# HL1102.net
KiCad netlist of a schematic drawn in Altium Designer
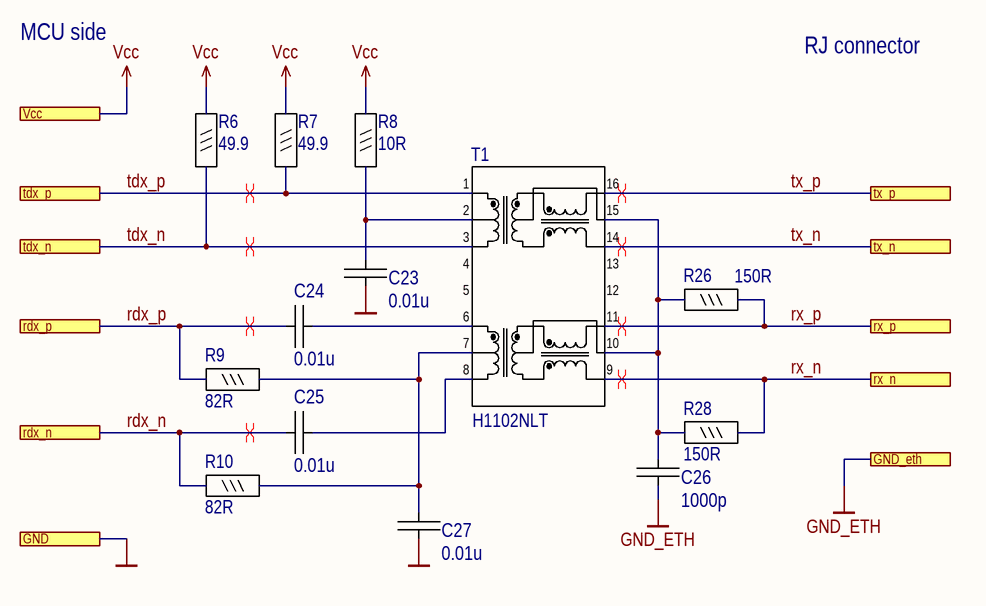
[diagram p0: HL1102.SchDoc]

(export (version "E")
  (design (tool "Eeschema 10.0.6"))
  (components
    (comp (ref "C23")
      (value "0.01u")
      (footprint "C0603_IPC")
      (description "0.01uF ±10% 50V Ceramic Capacitor X7R 0603 (1608 Metric)")
      (fields (field (name "PARTNUMBER") "0.01u 50V") (field (name "MPN") "CC0603KRX7R9BB103"))
      (libsource (lib "DB_res_cap_ind") (part "C0603_GOST"))
    )
    (comp (ref "C24")
      (value "0.01u")
      (footprint "C0603_IPC")
      (description "0.01uF ±10% 50V Ceramic Capacitor X7R 0603 (1608 Metric)")
      (fields (field (name "PARTNUMBER") "0.01u 50V") (field (name "MPN") "CC0603KRX7R9BB103"))
      (libsource (lib "DB_res_cap_ind") (part "C0603_GOST"))
    )
    (comp (ref "C25")
      (value "0.01u")
      (footprint "C0603_IPC")
      (description "0.01uF ±10% 50V Ceramic Capacitor X7R 0603 (1608 Metric)")
      (fields (field (name "PARTNUMBER") "0.01u 50V") (field (name "MPN") "CC0603KRX7R9BB103"))
      (libsource (lib "DB_res_cap_ind") (part "C0603_GOST"))
    )
    (comp (ref "C26")
      (value "1000p")
      (footprint "C1206_IPC")
      (description "1000pF ±5% 2000V (2kV) Ceramic Capacitor C0G, NP0 1206 (3216 Metric)")
      (fields (field (name "PARTNUMBER") "1000p 2kV") (field (name "MPN") "CC1206KKX7RDBB102"))
      (libsource (lib "DB_res_cap_ind") (part "C0603_GOST"))
    )
    (comp (ref "C27")
      (value "0.01u")
      (footprint "C0603_IPC")
      (description "0.01uF ±10% 50V Ceramic Capacitor X7R 0603 (1608 Metric)")
      (fields (field (name "PARTNUMBER") "0.01u 50V") (field (name "MPN") "CC0603KRX7R9BB103"))
      (libsource (lib "DB_res_cap_ind") (part "C0603_GOST"))
    )
    (comp (ref "R6")
      (value "49.9")
      (footprint "R0603")
      (description "49.9 Ohms ±1% 0.1W, 1/10W Chip Resistor 0603 (1608 Metric) Moisture Resistant Thick Film")
      (fields (field (name "MPN") "RC0603FR-0749R9L") (field (name "TOLERANCE") "1%"))
      (libsource (lib "DB_res_cap_ind") (part "R0603"))
    )
    (comp (ref "R7")
      (value "49.9")
      (footprint "R0603")
      (description "49.9 Ohms ±1% 0.1W, 1/10W Chip Resistor 0603 (1608 Metric) Moisture Resistant Thick Film")
      (fields (field (name "MPN") "RC0603FR-0749R9L") (field (name "TOLERANCE") "1%"))
      (libsource (lib "DB_res_cap_ind") (part "R0603"))
    )
    (comp (ref "R8")
      (value "10R")
      (footprint "R0603")
      (description "10 Ohms ±1% 0.1W, 1/10W Chip Resistor 0603 (1608 Metric) Moisture Resistant Thick Film")
      (fields (field (name "MPN") "RC0603FR-0710RL") (field (name "TOLERANCE") "1%"))
      (libsource (lib "DB_res_cap_ind") (part "R0603"))
    )
    (comp (ref "R9")
      (value "82R")
      (footprint "R0603")
      (description "82 Ohms ±1% 0.1W, 1/10W Chip Resistor 0603 (1608 Metric) Moisture Resistant Thick Film")
      (fields (field (name "MPN") "RC0603FR-0782RL") (field (name "TOLERANCE") "1%"))
      (libsource (lib "DB_res_cap_ind") (part "R0603"))
    )
    (comp (ref "R10")
      (value "82R")
      (footprint "R0603")
      (description "82 Ohms ±1% 0.1W, 1/10W Chip Resistor 0603 (1608 Metric) Moisture Resistant Thick Film")
      (fields (field (name "MPN") "RC0603FR-0782RL") (field (name "TOLERANCE") "1%"))
      (libsource (lib "DB_res_cap_ind") (part "R0603"))
    )
    (comp (ref "R26")
      (value "150R")
      (footprint "R0603")
      (description "150 Ohms ±1% 0.1W, 1/10W Chip Resistor 0603 (1608 Metric) Moisture Resistant Thick Film")
      (fields (field (name "MPN") "RC0603FR-07150RL") (field (name "TOLERANCE") "1%"))
      (libsource (lib "DB_res_cap_ind") (part "R0603"))
    )
    (comp (ref "R28")
      (value "150R")
      (footprint "R0603")
      (description "150 Ohms ±1% 0.1W, 1/10W Chip Resistor 0603 (1608 Metric) Moisture Resistant Thick Film")
      (fields (field (name "MPN") "RC0603FR-07150RL") (field (name "TOLERANCE") "1%"))
      (libsource (lib "DB_res_cap_ind") (part "R0603"))
    )
    (comp (ref "T1")
      (value "H1102NLT")
      (footprint "H1102NLT")
      (fields (field (name "MANUFACTURER") "Pulse Electronics Network"))
      (libsource (lib "DB_the_rest") (part "H1102NLT"))
    )
  )
  (nets
    (net (code "1") (name "/rdx_n") (class "Default")
      (node (ref "C25") (pin "1") (pinfunction "1_1") (pintype "passive"))
      (node (ref "R10") (pin "1") (pinfunction "1_1") (pintype "passive"))
    )
    (net (code "2") (name "/rdx_p") (class "Default")
      (node (ref "C24") (pin "1") (pinfunction "1_1") (pintype "passive"))
      (node (ref "R9") (pin "1") (pinfunction "1_1") (pintype "passive"))
    )
    (net (code "3") (name "/rx_n") (class "Default")
      (node (ref "R28") (pin "2") (pinfunction "2_2") (pintype "passive"))
      (node (ref "T1") (pin "9") (pinfunction "9_9") (pintype "passive"))
    )
    (net (code "4") (name "/rx_p") (class "Default")
      (node (ref "R26") (pin "2") (pinfunction "2_2") (pintype "passive"))
      (node (ref "T1") (pin "11") (pinfunction "11_11") (pintype "passive"))
    )
    (net (code "5") (name "/tdx_n") (class "Default")
      (node (ref "R6") (pin "1") (pinfunction "1_1") (pintype "passive"))
      (node (ref "T1") (pin "3") (pinfunction "3_3") (pintype "passive"))
    )
    (net (code "6") (name "/tdx_p") (class "Default")
      (node (ref "R7") (pin "1") (pinfunction "1_1") (pintype "passive"))
      (node (ref "T1") (pin "1") (pinfunction "1_1") (pintype "passive"))
    )
    (net (code "7") (name "/tx_n") (class "Default")
      (node (ref "T1") (pin "14") (pinfunction "14_14") (pintype "passive"))
    )
    (net (code "8") (name "/tx_p") (class "Default")
      (node (ref "T1") (pin "16") (pinfunction "16_16") (pintype "passive"))
    )
    (net (code "9") (name "GND") (class "Default")
      (node (ref "C23") (pin "1") (pinfunction "1_1") (pintype "passive"))
      (node (ref "C27") (pin "1") (pinfunction "1_1") (pintype "passive"))
    )
    (net (code "10") (name "GND_ETH") (class "Default")
      (node (ref "C26") (pin "2") (pinfunction "2_2") (pintype "passive"))
    )
    (net (code "11") (name "Net-(C23-Pad2)") (class "Default")
      (node (ref "C23") (pin "2") (pinfunction "2_2") (pintype "passive"))
      (node (ref "R8") (pin "1") (pinfunction "1_1") (pintype "passive"))
      (node (ref "T1") (pin "2") (pinfunction "2_2") (pintype "passive"))
    )
    (net (code "12") (name "Net-(C24-Pad2)") (class "Default")
      (node (ref "C24") (pin "2") (pinfunction "2_2") (pintype "passive"))
      (node (ref "T1") (pin "6") (pinfunction "6_6") (pintype "passive"))
    )
    (net (code "13") (name "Net-(C25-Pad2)") (class "Default")
      (node (ref "C25") (pin "2") (pinfunction "2_2") (pintype "passive"))
      (node (ref "T1") (pin "8") (pinfunction "8_8") (pintype "passive"))
    )
    (net (code "14") (name "Net-(C26-Pad1)") (class "Default")
      (node (ref "C26") (pin "1") (pinfunction "1_1") (pintype "passive"))
      (node (ref "R26") (pin "1") (pinfunction "1_1") (pintype "passive"))
      (node (ref "R28") (pin "1") (pinfunction "1_1") (pintype "passive"))
      (node (ref "T1") (pin "10") (pinfunction "10_10") (pintype "passive"))
      (node (ref "T1") (pin "15") (pinfunction "15_15") (pintype "passive"))
    )
    (net (code "15") (name "Net-(C27-Pad2)") (class "Default")
      (node (ref "C27") (pin "2") (pinfunction "2_2") (pintype "passive"))
      (node (ref "R10") (pin "2") (pinfunction "2_2") (pintype "passive"))
      (node (ref "R9") (pin "2") (pinfunction "2_2") (pintype "passive"))
      (node (ref "T1") (pin "7") (pinfunction "7_7") (pintype "passive"))
    )
    (net (code "16") (name "Vcc") (class "Default")
      (node (ref "R6") (pin "2") (pinfunction "2_2") (pintype "passive"))
      (node (ref "R7") (pin "2") (pinfunction "2_2") (pintype "passive"))
      (node (ref "R8") (pin "2") (pinfunction "2_2") (pintype "passive"))
    )
    (net (code "17") (name "unconnected-(T1-Pad4)") (class "Default")
      (node (ref "T1") (pin "4") (pinfunction "4_4") (pintype "passive"))
    )
    (net (code "18") (name "unconnected-(T1-Pad5)") (class "Default")
      (node (ref "T1") (pin "5") (pinfunction "5_5") (pintype "passive"))
    )
    (net (code "19") (name "unconnected-(T1-Pad12)") (class "Default")
      (node (ref "T1") (pin "12") (pinfunction "12_12") (pintype "passive"))
    )
    (net (code "20") (name "unconnected-(T1-Pad13)") (class "Default")
      (node (ref "T1") (pin "13") (pinfunction "13_13") (pintype "passive"))
    )
  )
)
